# ArdUNO.net
KiCad netlist of a schematic drawn in EAGLE
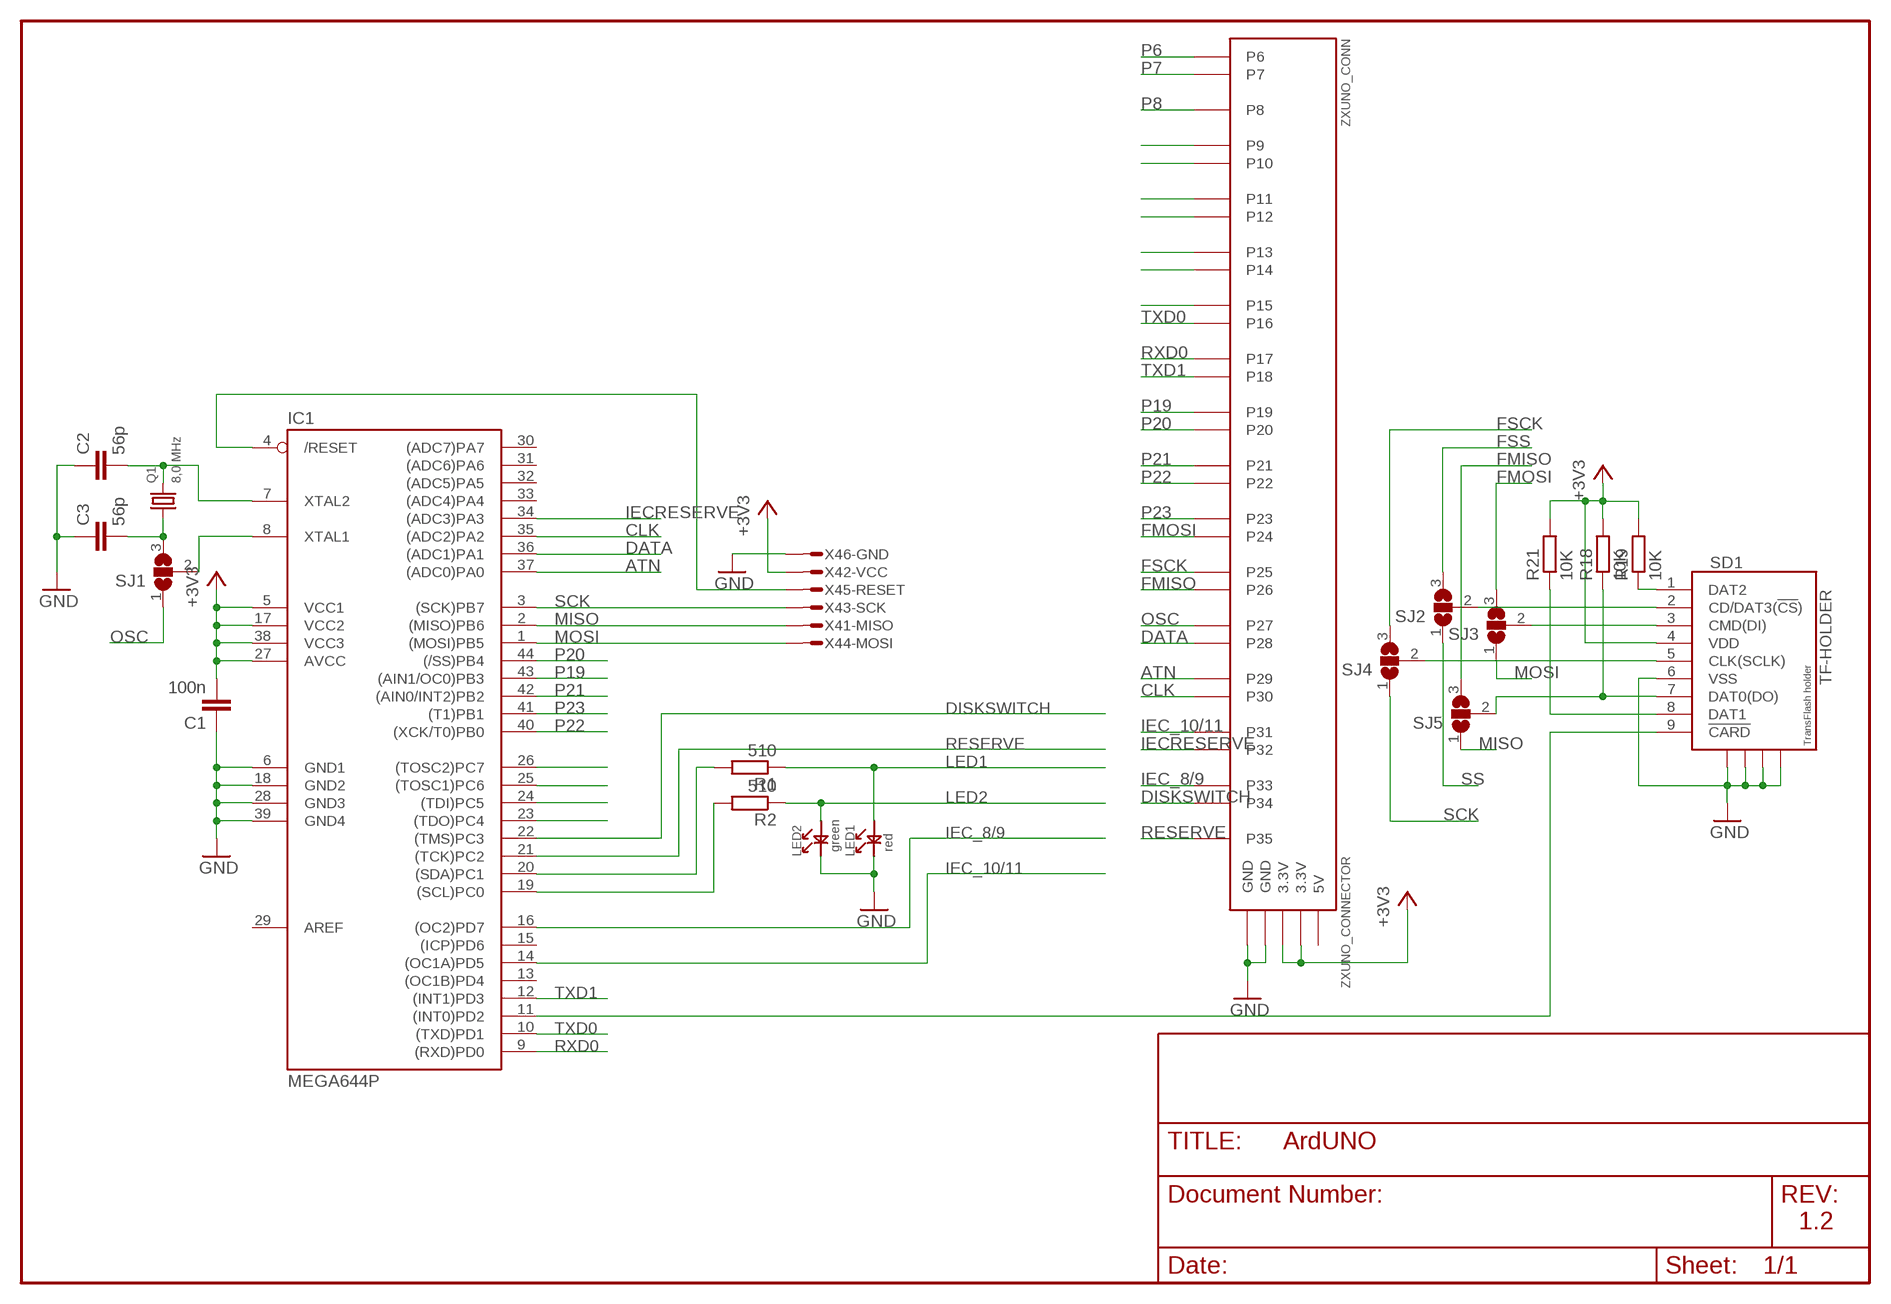
[diagram p0: schematic, sheet 1]

(export (version "E")
  (design (tool "Eeschema 10.0.6"))
  (components
    (comp (ref "C1")
      (value "100n")
      (footprint "eagle-import:C0805")
      (libsource (lib "eagle-import") (part "C-EUC0805"))
    )
    (comp (ref "C2")
      (value "56p")
      (footprint "eagle-import:C0805")
      (libsource (lib "eagle-import") (part "C-EUC0805"))
    )
    (comp (ref "C3")
      (value "56p")
      (footprint "eagle-import:C0805")
      (libsource (lib "eagle-import") (part "C-EUC0805"))
    )
    (comp (ref "IC1")
      (value "MEGA644P")
      (footprint "eagle-import:TQFP44")
      (libsource (lib "eagle-import") (part "MEGA16/32TQFP"))
    )
    (comp (ref "LED1")
      (value "red")
      (footprint "eagle-import:LED0805")
      (libsource (lib "eagle-import") (part "LED0805"))
    )
    (comp (ref "LED2")
      (value "green")
      (footprint "eagle-import:LED0805")
      (libsource (lib "eagle-import") (part "LED0805"))
    )
    (comp (ref "Q1")
      (value "8,0 MHz")
      (footprint "eagle-import:HC49_S")
      (libsource (lib "eagle-import") (part "HC49"))
    )
    (comp (ref "R1")
      (value "510")
      (footprint "eagle-import:R0805")
      (libsource (lib "eagle-import") (part "R-EU_R0805"))
    )
    (comp (ref "R2")
      (value "510")
      (footprint "eagle-import:R0805")
      (libsource (lib "eagle-import") (part "R-EU_R0805"))
    )
    (comp (ref "R18")
      (value "10K")
      (footprint "eagle-import:R0805")
      (libsource (lib "eagle-import") (part "R-EU_R0805"))
    )
    (comp (ref "R19")
      (value "10K")
      (footprint "eagle-import:R0805")
      (libsource (lib "eagle-import") (part "R-EU_R0805"))
    )
    (comp (ref "R21")
      (value "10K")
      (footprint "eagle-import:R0805")
      (libsource (lib "eagle-import") (part "R-EU_R0805"))
    )
    (comp (ref "SD1")
      (value "TF-HOLDER")
      (footprint "eagle-import:TF-PULL")
      (libsource (lib "eagle-import") (part "TF-HOLDER"))
    )
    (comp (ref "SJ1")
      (value "SJ2W")
      (footprint "eagle-import:SJ_2")
      (libsource (lib "eagle-import") (part "SJ2W"))
    )
    (comp (ref "SJ2")
      (value "SJ2W")
      (footprint "eagle-import:SJ_2")
      (libsource (lib "eagle-import") (part "SJ2W"))
    )
    (comp (ref "SJ3")
      (value "SJ2W")
      (footprint "eagle-import:SJ_2")
      (libsource (lib "eagle-import") (part "SJ2W"))
    )
    (comp (ref "SJ4")
      (value "SJ2W")
      (footprint "eagle-import:SJ_2")
      (libsource (lib "eagle-import") (part "SJ2W"))
    )
    (comp (ref "SJ5")
      (value "SJ2W")
      (footprint "eagle-import:SJ_2")
      (libsource (lib "eagle-import") (part "SJ2W"))
    )
    (comp (ref "X4")
      (value "AVR-ISP_1X6")
      (footprint "eagle-import:1X6_ISP")
      (libsource (lib "eagle-import") (part "AVR-ISP_1X6"))
    )
    (comp (ref "ZXUNO_CONN")
      (value "ZXUNO_CONNECTOR")
      (footprint "eagle-import:ZXUNO_CONNECTOR")
      (libsource (lib "eagle-import") (part "ZXUNO_CONNECTOR"))
    )
  )
  (nets
    (net (code "1") (name "+3V3") (class "Default")
      (node (ref "C1") (pin "2") (pinfunction "2_2") (pintype "passive"))
      (node (ref "IC1") (pin "17") (pinfunction "VCC2_17") (pintype "power_in"))
      (node (ref "IC1") (pin "27") (pinfunction "AVCC_27") (pintype "power_in"))
      (node (ref "IC1") (pin "38") (pinfunction "VCC3_38") (pintype "power_in"))
      (node (ref "IC1") (pin "5") (pinfunction "VCC1_5") (pintype "power_in"))
      (node (ref "R18") (pin "2") (pinfunction "2_2") (pintype "passive"))
      (node (ref "R19") (pin "2") (pinfunction "2_2") (pintype "passive"))
      (node (ref "R21") (pin "2") (pinfunction "2_2") (pintype "passive"))
      (node (ref "SD1") (pin "4") (pinfunction "VDD_4") (pintype "power_in"))
      (node (ref "X4") (pin "2") (pinfunction "S_2") (pintype "passive"))
      (node (ref "ZXUNO_CONN") (pin "3.3V@1") (pinfunction "3.3V_3.3V@1") (pintype "power_in"))
      (node (ref "ZXUNO_CONN") (pin "3.3V@2") (pinfunction "3.3V_3.3V@2") (pintype "power_in"))
    )
    (net (code "2") (name "/5V") (class "Default")
      (node (ref "ZXUNO_CONN") (pin "5V") (pinfunction "5V_5V") (pintype "power_in"))
    )
    (net (code "3") (name "/ATN") (class "Default")
      (node (ref "IC1") (pin "37") (pinfunction "(ADC0)PA0_37") (pintype "bidirectional"))
      (node (ref "ZXUNO_CONN") (pin "P29") (pinfunction "P29_P29") (pintype "bidirectional"))
    )
    (net (code "4") (name "/CLK") (class "Default")
      (node (ref "IC1") (pin "35") (pinfunction "(ADC2)PA2_35") (pintype "bidirectional"))
      (node (ref "ZXUNO_CONN") (pin "P30") (pinfunction "P30_P30") (pintype "bidirectional"))
    )
    (net (code "5") (name "/DATA") (class "Default")
      (node (ref "IC1") (pin "36") (pinfunction "(ADC1)PA1_36") (pintype "bidirectional"))
      (node (ref "ZXUNO_CONN") (pin "P28") (pinfunction "P28_P28") (pintype "bidirectional"))
    )
    (net (code "6") (name "/DISKSWITCH") (class "Default")
      (node (ref "IC1") (pin "22") (pinfunction "(TMS)PC3_22") (pintype "bidirectional"))
      (node (ref "ZXUNO_CONN") (pin "P34") (pinfunction "P34_P34") (pintype "bidirectional"))
    )
    (net (code "7") (name "/FMISO") (class "Default")
      (node (ref "SJ5") (pin "3") (pinfunction "3_3") (pintype "passive"))
      (node (ref "ZXUNO_CONN") (pin "P26") (pinfunction "P26_P26") (pintype "bidirectional"))
    )
    (net (code "8") (name "/FMOSI") (class "Default")
      (node (ref "SJ3") (pin "3") (pinfunction "3_3") (pintype "passive"))
      (node (ref "ZXUNO_CONN") (pin "P24") (pinfunction "P24_P24") (pintype "bidirectional"))
    )
    (net (code "9") (name "/FSCK") (class "Default")
      (node (ref "SJ4") (pin "3") (pinfunction "3_3") (pintype "passive"))
      (node (ref "ZXUNO_CONN") (pin "P25") (pinfunction "P25_P25") (pintype "bidirectional"))
    )
    (net (code "10") (name "/FSS") (class "Default")
      (node (ref "SJ2") (pin "3") (pinfunction "3_3") (pintype "passive"))
    )
    (net (code "11") (name "/IECRESERVE") (class "Default")
      (node (ref "IC1") (pin "34") (pinfunction "(ADC3)PA3_34") (pintype "bidirectional"))
      (node (ref "ZXUNO_CONN") (pin "P32") (pinfunction "P32_P32") (pintype "bidirectional"))
    )
    (net (code "12") (name "/IEC_8{slash}9") (class "Default")
      (node (ref "IC1") (pin "16") (pinfunction "(OC2)PD7_16") (pintype "bidirectional"))
      (node (ref "ZXUNO_CONN") (pin "P33") (pinfunction "P33_P33") (pintype "bidirectional"))
    )
    (net (code "13") (name "/IEC_10{slash}11") (class "Default")
      (node (ref "IC1") (pin "14") (pinfunction "(OC1A)PD5_14") (pintype "bidirectional"))
      (node (ref "ZXUNO_CONN") (pin "P31") (pinfunction "P31_P31") (pintype "bidirectional"))
    )
    (net (code "14") (name "/LED1") (class "Default")
      (node (ref "LED1") (pin "2") (pinfunction "2_2") (pintype "passive"))
      (node (ref "R1") (pin "1") (pinfunction "1_1") (pintype "passive"))
    )
    (net (code "15") (name "/LED2") (class "Default")
      (node (ref "LED2") (pin "2") (pinfunction "2_2") (pintype "passive"))
      (node (ref "R2") (pin "1") (pinfunction "1_1") (pintype "passive"))
    )
    (net (code "16") (name "/MISO") (class "Default")
      (node (ref "IC1") (pin "2") (pinfunction "(MISO)PB6_2") (pintype "bidirectional"))
      (node (ref "SJ5") (pin "1") (pinfunction "1_1") (pintype "passive"))
      (node (ref "X4") (pin "1") (pinfunction "S_1") (pintype "passive"))
    )
    (net (code "17") (name "/MOSI") (class "Default")
      (node (ref "IC1") (pin "1") (pinfunction "(MOSI)PB5_1") (pintype "bidirectional"))
      (node (ref "SJ3") (pin "1") (pinfunction "1_1") (pintype "passive"))
      (node (ref "X4") (pin "4") (pinfunction "S_4") (pintype "passive"))
    )
    (net (code "18") (name "/OSC") (class "Default")
      (node (ref "SJ1") (pin "1") (pinfunction "1_1") (pintype "passive"))
      (node (ref "ZXUNO_CONN") (pin "P27") (pinfunction "P27_P27") (pintype "bidirectional"))
    )
    (net (code "19") (name "/P6") (class "Default")
      (node (ref "ZXUNO_CONN") (pin "P6") (pinfunction "P6_P6") (pintype "bidirectional"))
    )
    (net (code "20") (name "/P7") (class "Default")
      (node (ref "ZXUNO_CONN") (pin "P7") (pinfunction "P7_P7") (pintype "bidirectional"))
    )
    (net (code "21") (name "/P8") (class "Default")
      (node (ref "ZXUNO_CONN") (pin "P8") (pinfunction "P8_P8") (pintype "bidirectional"))
    )
    (net (code "22") (name "/P19") (class "Default")
      (node (ref "IC1") (pin "43") (pinfunction "(AIN1/OC0)PB3_43") (pintype "bidirectional"))
      (node (ref "ZXUNO_CONN") (pin "P19") (pinfunction "P19_P19") (pintype "bidirectional"))
    )
    (net (code "23") (name "/P20") (class "Default")
      (node (ref "IC1") (pin "44") (pinfunction "(/SS)PB4_44") (pintype "bidirectional"))
      (node (ref "ZXUNO_CONN") (pin "P20") (pinfunction "P20_P20") (pintype "bidirectional"))
    )
    (net (code "24") (name "/P21") (class "Default")
      (node (ref "IC1") (pin "42") (pinfunction "(AIN0/INT2)PB2_42") (pintype "bidirectional"))
      (node (ref "ZXUNO_CONN") (pin "P21") (pinfunction "P21_P21") (pintype "bidirectional"))
    )
    (net (code "25") (name "/P22") (class "Default")
      (node (ref "IC1") (pin "40") (pinfunction "(XCK/T0)PB0_40") (pintype "bidirectional"))
      (node (ref "ZXUNO_CONN") (pin "P22") (pinfunction "P22_P22") (pintype "bidirectional"))
    )
    (net (code "26") (name "/P23") (class "Default")
      (node (ref "IC1") (pin "41") (pinfunction "(T1)PB1_41") (pintype "bidirectional"))
      (node (ref "ZXUNO_CONN") (pin "P23") (pinfunction "P23_P23") (pintype "bidirectional"))
    )
    (net (code "27") (name "/RESERVE") (class "Default")
      (node (ref "IC1") (pin "21") (pinfunction "(TCK)PC2_21") (pintype "bidirectional"))
      (node (ref "ZXUNO_CONN") (pin "P35") (pinfunction "P35_P35") (pintype "bidirectional"))
    )
    (net (code "28") (name "/RXD0") (class "Default")
      (node (ref "IC1") (pin "9") (pinfunction "(RXD)PD0_9") (pintype "bidirectional"))
      (node (ref "ZXUNO_CONN") (pin "P17") (pinfunction "P17_P17") (pintype "bidirectional"))
    )
    (net (code "29") (name "/SCK") (class "Default")
      (node (ref "IC1") (pin "3") (pinfunction "(SCK)PB7_3") (pintype "bidirectional"))
      (node (ref "SJ4") (pin "1") (pinfunction "1_1") (pintype "passive"))
      (node (ref "X4") (pin "3") (pinfunction "S_3") (pintype "passive"))
    )
    (net (code "30") (name "/SS") (class "Default")
      (node (ref "SJ2") (pin "1") (pinfunction "1_1") (pintype "passive"))
    )
    (net (code "31") (name "/TXD0") (class "Default")
      (node (ref "IC1") (pin "10") (pinfunction "(TXD)PD1_10") (pintype "bidirectional"))
      (node (ref "ZXUNO_CONN") (pin "P16") (pinfunction "P16_P16") (pintype "bidirectional"))
    )
    (net (code "32") (name "/TXD1") (class "Default")
      (node (ref "IC1") (pin "12") (pinfunction "(INT1)PD3_12") (pintype "bidirectional"))
      (node (ref "ZXUNO_CONN") (pin "P18") (pinfunction "P18_P18") (pintype "bidirectional"))
    )
    (net (code "33") (name "GND") (class "Default")
      (node (ref "C1") (pin "1") (pinfunction "1_1") (pintype "passive"))
      (node (ref "C2") (pin "1") (pinfunction "1_1") (pintype "passive"))
      (node (ref "C3") (pin "1") (pinfunction "1_1") (pintype "passive"))
      (node (ref "IC1") (pin "18") (pinfunction "GND2_18") (pintype "power_in"))
      (node (ref "IC1") (pin "28") (pinfunction "GND3_28") (pintype "power_in"))
      (node (ref "IC1") (pin "39") (pinfunction "GND4_39") (pintype "power_in"))
      (node (ref "IC1") (pin "6") (pinfunction "GND1_6") (pintype "power_in"))
      (node (ref "LED1") (pin "1") (pinfunction "1_1") (pintype "passive"))
      (node (ref "LED2") (pin "1") (pinfunction "1_1") (pintype "passive"))
      (node (ref "SD1") (pin "6") (pinfunction "VSS_6") (pintype "power_in"))
      (node (ref "SD1") (pin "S1") (pinfunction "S1_S1") (pintype "passive"))
      (node (ref "SD1") (pin "S2") (pinfunction "S2_S2") (pintype "passive"))
      (node (ref "SD1") (pin "S3") (pinfunction "S3_S3") (pintype "passive"))
      (node (ref "SD1") (pin "S4") (pinfunction "S4_S4") (pintype "passive"))
      (node (ref "X4") (pin "6") (pinfunction "S_6") (pintype "passive"))
      (node (ref "ZXUNO_CONN") (pin "GND@1") (pinfunction "GND_GND@1") (pintype "power_in"))
      (node (ref "ZXUNO_CONN") (pin "GND@2") (pinfunction "GND_GND@2") (pintype "power_in"))
    )
    (net (code "34") (name "Net-(C3-Pad2)") (class "Default")
      (node (ref "C3") (pin "2") (pinfunction "2_2") (pintype "passive"))
      (node (ref "Q1") (pin "1") (pinfunction "1_1") (pintype "passive"))
      (node (ref "SJ1") (pin "3") (pinfunction "3_3") (pintype "passive"))
    )
    (net (code "35") (name "Net-(IC1-(INT0)PD2)") (class "Default")
      (node (ref "IC1") (pin "11") (pinfunction "(INT0)PD2_11") (pintype "bidirectional"))
      (node (ref "SD1") (pin "9") (pinfunction "~{CARD}_9") (pintype "passive"))
    )
    (net (code "36") (name "Net-(IC1-(SCL)PC0)") (class "Default")
      (node (ref "IC1") (pin "19") (pinfunction "(SCL)PC0_19") (pintype "bidirectional"))
      (node (ref "R2") (pin "2") (pinfunction "2_2") (pintype "passive"))
    )
    (net (code "37") (name "Net-(IC1-(SDA)PC1)") (class "Default")
      (node (ref "IC1") (pin "20") (pinfunction "(SDA)PC1_20") (pintype "bidirectional"))
      (node (ref "R1") (pin "2") (pinfunction "2_2") (pintype "passive"))
    )
    (net (code "38") (name "Net-(IC1-XTAL1)") (class "Default")
      (node (ref "IC1") (pin "8") (pinfunction "XTAL1_8") (pintype "input"))
      (node (ref "SJ1") (pin "2") (pinfunction "2_2") (pintype "passive"))
    )
    (net (code "39") (name "Net-(IC1-XTAL2)") (class "Default")
      (node (ref "C2") (pin "2") (pinfunction "2_2") (pintype "passive"))
      (node (ref "IC1") (pin "7") (pinfunction "XTAL2_7") (pintype "input"))
      (node (ref "Q1") (pin "2") (pinfunction "2_2") (pintype "passive"))
    )
    (net (code "40") (name "Net-(IC1-{slash}RESET)") (class "Default")
      (node (ref "IC1") (pin "4") (pinfunction "/RESET_4") (pintype "input"))
      (node (ref "X4") (pin "5") (pinfunction "S_5") (pintype "passive"))
    )
    (net (code "41") (name "Net-(SD1-CD{slash}DAT3(~{CS}))") (class "Default")
      (node (ref "SD1") (pin "2") (pinfunction "CD/DAT3(~{CS})_2") (pintype "bidirectional"))
      (node (ref "SJ2") (pin "2") (pinfunction "2_2") (pintype "passive"))
    )
    (net (code "42") (name "Net-(SD1-CLK(SCLK))") (class "Default")
      (node (ref "SD1") (pin "5") (pinfunction "CLK(SCLK)_5") (pintype "input"))
      (node (ref "SJ4") (pin "2") (pinfunction "2_2") (pintype "passive"))
    )
    (net (code "43") (name "Net-(SD1-CMD(DI))") (class "Default")
      (node (ref "SD1") (pin "3") (pinfunction "CMD(DI)_3") (pintype "bidirectional"))
      (node (ref "SJ3") (pin "2") (pinfunction "2_2") (pintype "passive"))
    )
    (net (code "44") (name "Net-(SD1-DAT0(DO))") (class "Default")
      (node (ref "R18") (pin "1") (pinfunction "1_1") (pintype "passive"))
      (node (ref "SD1") (pin "7") (pinfunction "DAT0(DO)_7") (pintype "bidirectional"))
      (node (ref "SJ5") (pin "2") (pinfunction "2_2") (pintype "passive"))
    )
    (net (code "45") (name "Net-(SD1-DAT1)") (class "Default")
      (node (ref "R21") (pin "1") (pinfunction "1_1") (pintype "passive"))
      (node (ref "SD1") (pin "8") (pinfunction "DAT1_8") (pintype "bidirectional"))
    )
    (net (code "46") (name "Net-(SD1-DAT2)") (class "Default")
      (node (ref "R19") (pin "1") (pinfunction "1_1") (pintype "passive"))
      (node (ref "SD1") (pin "1") (pinfunction "DAT2_1") (pintype "bidirectional"))
    )
    (net (code "47") (name "unconnected-(IC1-(ADC4)PA4-Pad33)") (class "Default")
      (node (ref "IC1") (pin "33") (pinfunction "(ADC4)PA4_33") (pintype "bidirectional"))
    )
    (net (code "48") (name "unconnected-(IC1-(ADC5)PA5-Pad32)") (class "Default")
      (node (ref "IC1") (pin "32") (pinfunction "(ADC5)PA5_32") (pintype "bidirectional"))
    )
    (net (code "49") (name "unconnected-(IC1-(ADC6)PA6-Pad31)") (class "Default")
      (node (ref "IC1") (pin "31") (pinfunction "(ADC6)PA6_31") (pintype "bidirectional"))
    )
    (net (code "50") (name "unconnected-(IC1-(ADC7)PA7-Pad30)") (class "Default")
      (node (ref "IC1") (pin "30") (pinfunction "(ADC7)PA7_30") (pintype "bidirectional"))
    )
    (net (code "51") (name "unconnected-(IC1-(ICP)PD6-Pad15)") (class "Default")
      (node (ref "IC1") (pin "15") (pinfunction "(ICP)PD6_15") (pintype "bidirectional"))
    )
    (net (code "52") (name "unconnected-(IC1-(OC1B)PD4-Pad13)") (class "Default")
      (node (ref "IC1") (pin "13") (pinfunction "(OC1B)PD4_13") (pintype "bidirectional"))
    )
    (net (code "53") (name "unconnected-(IC1-(TDI)PC5-Pad24)") (class "Default")
      (node (ref "IC1") (pin "24") (pinfunction "(TDI)PC5_24") (pintype "bidirectional"))
    )
    (net (code "54") (name "unconnected-(IC1-(TDO)PC4-Pad23)") (class "Default")
      (node (ref "IC1") (pin "23") (pinfunction "(TDO)PC4_23") (pintype "bidirectional"))
    )
    (net (code "55") (name "unconnected-(IC1-(TOSC1)PC6-Pad25)") (class "Default")
      (node (ref "IC1") (pin "25") (pinfunction "(TOSC1)PC6_25") (pintype "bidirectional"))
    )
    (net (code "56") (name "unconnected-(IC1-(TOSC2)PC7-Pad26)") (class "Default")
      (node (ref "IC1") (pin "26") (pinfunction "(TOSC2)PC7_26") (pintype "bidirectional"))
    )
    (net (code "57") (name "unconnected-(IC1-AREF-Pad29)") (class "Default")
      (node (ref "IC1") (pin "29") (pinfunction "AREF_29") (pintype "bidirectional"))
    )
    (net (code "58") (name "unconnected-(ZXUNO_CONN-PadP9)") (class "Default")
      (node (ref "ZXUNO_CONN") (pin "P9") (pinfunction "P9_P9") (pintype "bidirectional"))
    )
    (net (code "59") (name "unconnected-(ZXUNO_CONN-PadP10)") (class "Default")
      (node (ref "ZXUNO_CONN") (pin "P10") (pinfunction "P10_P10") (pintype "bidirectional"))
    )
    (net (code "60") (name "unconnected-(ZXUNO_CONN-PadP11)") (class "Default")
      (node (ref "ZXUNO_CONN") (pin "P11") (pinfunction "P11_P11") (pintype "bidirectional"))
    )
    (net (code "61") (name "unconnected-(ZXUNO_CONN-PadP12)") (class "Default")
      (node (ref "ZXUNO_CONN") (pin "P12") (pinfunction "P12_P12") (pintype "bidirectional"))
    )
    (net (code "62") (name "unconnected-(ZXUNO_CONN-PadP13)") (class "Default")
      (node (ref "ZXUNO_CONN") (pin "P13") (pinfunction "P13_P13") (pintype "bidirectional"))
    )
    (net (code "63") (name "unconnected-(ZXUNO_CONN-PadP14)") (class "Default")
      (node (ref "ZXUNO_CONN") (pin "P14") (pinfunction "P14_P14") (pintype "bidirectional"))
    )
    (net (code "64") (name "unconnected-(ZXUNO_CONN-PadP15)") (class "Default")
      (node (ref "ZXUNO_CONN") (pin "P15") (pinfunction "P15_P15") (pintype "bidirectional"))
    )
  )
)
